# bidirectional-motor-driver.net
KiCad netlist of a schematic drawn in EAGLE
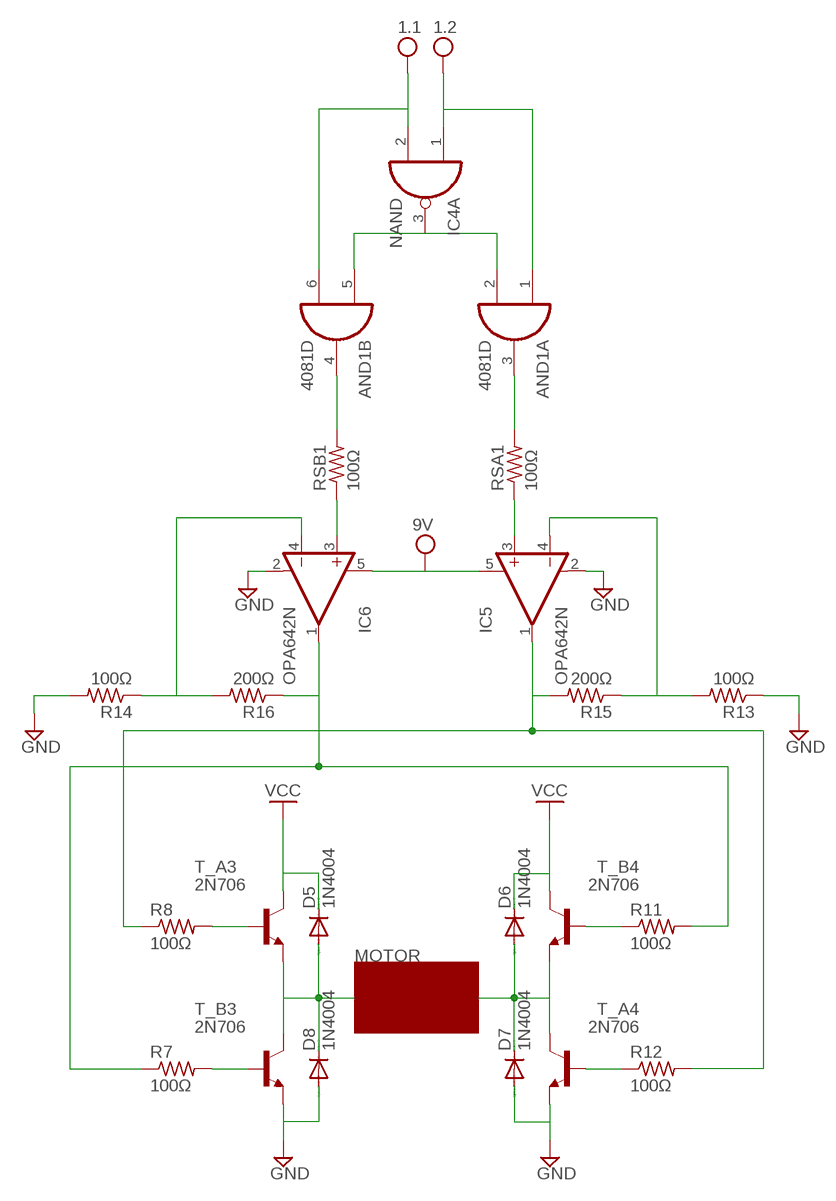
[diagram p0: schematic, sheet 1]

(export (version "E")
  (design (tool "Eeschema 10.0.6"))
  (components
    (comp (ref "AND1")
      (value "4081D")
      (footprint "eagle-import:SO14")
      (libsource (lib "eagle-import") (part "4081D"))
    )
    (comp (ref "D5")
      (value "1N4004")
      (footprint "eagle-import:DO41-10")
      (libsource (lib "eagle-import") (part "1N4004"))
    )
    (comp (ref "D6")
      (value "1N4004")
      (footprint "eagle-import:DO41-10")
      (libsource (lib "eagle-import") (part "1N4004"))
    )
    (comp (ref "D7")
      (value "1N4004")
      (footprint "eagle-import:DO41-10")
      (libsource (lib "eagle-import") (part "1N4004"))
    )
    (comp (ref "D8")
      (value "1N4004")
      (footprint "eagle-import:DO41-10")
      (libsource (lib "eagle-import") (part "1N4004"))
    )
    (comp (ref "IC4")
      (value "NAND")
      (footprint "eagle-import:SO14")
      (libsource (lib "eagle-import") (part "4011D"))
    )
    (comp (ref "IC5")
      (value "OPA642N")
      (footprint "eagle-import:SOT23-5")
      (libsource (lib "eagle-import") (part "OPA642N"))
    )
    (comp (ref "IC6")
      (value "OPA642N")
      (footprint "eagle-import:SOT23-5")
      (libsource (lib "eagle-import") (part "OPA642N"))
    )
    (comp (ref "R7")
      (value "100Ω")
      (footprint "eagle-import:0204V")
      (libsource (lib "eagle-import") (part "R-US_0204/2V"))
    )
    (comp (ref "R8")
      (value "100Ω")
      (footprint "eagle-import:0204V")
      (libsource (lib "eagle-import") (part "R-US_0204/2V"))
    )
    (comp (ref "R11")
      (value "100Ω")
      (footprint "eagle-import:0204V")
      (libsource (lib "eagle-import") (part "R-US_0204/2V"))
    )
    (comp (ref "R12")
      (value "100Ω")
      (footprint "eagle-import:0204V")
      (libsource (lib "eagle-import") (part "R-US_0204/2V"))
    )
    (comp (ref "R13")
      (value "100Ω")
      (footprint "eagle-import:0204V")
      (libsource (lib "eagle-import") (part "R-US_0204/2V"))
    )
    (comp (ref "R14")
      (value "100Ω")
      (footprint "eagle-import:0204V")
      (libsource (lib "eagle-import") (part "R-US_0204/2V"))
    )
    (comp (ref "R15")
      (value "200Ω")
      (footprint "eagle-import:0204V")
      (libsource (lib "eagle-import") (part "R-US_0204/2V"))
    )
    (comp (ref "R16")
      (value "200Ω")
      (footprint "eagle-import:0204V")
      (libsource (lib "eagle-import") (part "R-US_0204/2V"))
    )
    (comp (ref "RSA1")
      (value "100Ω")
      (footprint "eagle-import:0204V")
      (libsource (lib "eagle-import") (part "R-US_0204/2V"))
    )
    (comp (ref "RSB1")
      (value "100Ω")
      (footprint "eagle-import:0204V")
      (libsource (lib "eagle-import") (part "R-US_0204/2V"))
    )
    (comp (ref "T_A3")
      (value "2N706")
      (footprint "eagle-import:TO18")
      (libsource (lib "eagle-import") (part "2N706"))
    )
    (comp (ref "T_A4")
      (value "2N706")
      (footprint "eagle-import:TO18")
      (libsource (lib "eagle-import") (part "2N706"))
    )
    (comp (ref "T_B3")
      (value "2N706")
      (footprint "eagle-import:TO18")
      (libsource (lib "eagle-import") (part "2N706"))
    )
    (comp (ref "T_B4")
      (value "2N706")
      (footprint "eagle-import:TO18")
      (libsource (lib "eagle-import") (part "2N706"))
    )
  )
  (nets
    (net (code "1") (name "1.1") (class "Default")
      (node (ref "AND1") (pin "1") (pinfunction "I0_1") (pintype "input"))
      (node (ref "AND1") (pin "6") (pinfunction "I1_6") (pintype "input"))
      (node (ref "IC4") (pin "1") (pinfunction "I0_1") (pintype "input"))
      (node (ref "IC4") (pin "2") (pinfunction "I1_2") (pintype "input"))
    )
    (net (code "3") (name "GND") (class "Default")
      (node (ref "D7") (pin "A") (pinfunction "A_A") (pintype "passive"))
      (node (ref "D8") (pin "A") (pinfunction "A_A") (pintype "passive"))
      (node (ref "IC5") (pin "2") (pinfunction "V-_2") (pintype "power_in"))
      (node (ref "IC6") (pin "2") (pinfunction "V-_2") (pintype "power_in"))
      (node (ref "R13") (pin "1") (pinfunction "1_1") (pintype "passive"))
      (node (ref "R14") (pin "2") (pinfunction "2_2") (pintype "passive"))
      (node (ref "T_A4") (pin "1") (pinfunction "E_1") (pintype "passive"))
      (node (ref "T_B3") (pin "1") (pinfunction "E_1") (pintype "passive"))
    )
    (net (code "4") (name "Net-(AND1A-I1)") (class "Default")
      (node (ref "AND1") (pin "2") (pinfunction "I1_2") (pintype "input"))
      (node (ref "AND1") (pin "5") (pinfunction "I0_5") (pintype "input"))
      (node (ref "IC4") (pin "3") (pinfunction "O_3") (pintype "output"))
    )
    (net (code "5") (name "Net-(AND1A-O)") (class "Default")
      (node (ref "AND1") (pin "3") (pinfunction "O_3") (pintype "output"))
      (node (ref "RSA1") (pin "2") (pinfunction "2_2") (pintype "passive"))
    )
    (net (code "6") (name "Net-(AND1B-O)") (class "Default")
      (node (ref "AND1") (pin "4") (pinfunction "O_4") (pintype "output"))
      (node (ref "RSB1") (pin "2") (pinfunction "2_2") (pintype "passive"))
    )
    (net (code "7") (name "Net-(IC5-+IN)") (class "Default")
      (node (ref "IC5") (pin "3") (pinfunction "+IN_3") (pintype "input"))
      (node (ref "RSA1") (pin "1") (pinfunction "1_1") (pintype "passive"))
    )
    (net (code "8") (name "Net-(IC5-OUT)") (class "Default")
      (node (ref "IC5") (pin "1") (pinfunction "OUT_1") (pintype "output"))
      (node (ref "R12") (pin "2") (pinfunction "2_2") (pintype "passive"))
      (node (ref "R8") (pin "1") (pinfunction "1_1") (pintype "passive"))
    )
    (net (code "9") (name "Net-(IC5-V+)") (class "Default")
      (node (ref "IC5") (pin "5") (pinfunction "V+_5") (pintype "power_in"))
      (node (ref "IC6") (pin "5") (pinfunction "V+_5") (pintype "power_in"))
    )
    (net (code "10") (name "Net-(IC6-+IN)") (class "Default")
      (node (ref "IC6") (pin "3") (pinfunction "+IN_3") (pintype "input"))
      (node (ref "RSB1") (pin "1") (pinfunction "1_1") (pintype "passive"))
    )
    (net (code "11") (name "Net-(IC6-OUT)") (class "Default")
      (node (ref "IC6") (pin "1") (pinfunction "OUT_1") (pintype "output"))
      (node (ref "R11") (pin "2") (pinfunction "2_2") (pintype "passive"))
      (node (ref "R7") (pin "1") (pinfunction "1_1") (pintype "passive"))
    )
    (net (code "12") (name "Net-(R13-Pad2)") (class "Default")
      (node (ref "R13") (pin "2") (pinfunction "2_2") (pintype "passive"))
      (node (ref "R15") (pin "1") (pinfunction "1_1") (pintype "passive"))
    )
    (net (code "13") (name "Net-(R14-Pad1)") (class "Default")
      (node (ref "R14") (pin "1") (pinfunction "1_1") (pintype "passive"))
      (node (ref "R16") (pin "2") (pinfunction "2_2") (pintype "passive"))
    )
    (net (code "14") (name "Net-(T_A3-B)") (class "Default")
      (node (ref "R8") (pin "2") (pinfunction "2_2") (pintype "passive"))
      (node (ref "T_A3") (pin "2") (pinfunction "B_2") (pintype "passive"))
    )
    (net (code "15") (name "Net-(T_A3-E)") (class "Default")
      (node (ref "D5") (pin "A") (pinfunction "A_A") (pintype "passive"))
      (node (ref "D8") (pin "C") (pinfunction "C_C") (pintype "passive"))
      (node (ref "T_A3") (pin "1") (pinfunction "E_1") (pintype "passive"))
      (node (ref "T_B3") (pin "3") (pinfunction "C_3") (pintype "passive"))
    )
    (net (code "16") (name "Net-(T_A4-B)") (class "Default")
      (node (ref "R12") (pin "1") (pinfunction "1_1") (pintype "passive"))
      (node (ref "T_A4") (pin "2") (pinfunction "B_2") (pintype "passive"))
    )
    (net (code "17") (name "Net-(T_A4-C)") (class "Default")
      (node (ref "D6") (pin "A") (pinfunction "A_A") (pintype "passive"))
      (node (ref "D7") (pin "C") (pinfunction "C_C") (pintype "passive"))
      (node (ref "T_A4") (pin "3") (pinfunction "C_3") (pintype "passive"))
      (node (ref "T_B4") (pin "1") (pinfunction "E_1") (pintype "passive"))
    )
    (net (code "18") (name "Net-(T_B3-B)") (class "Default")
      (node (ref "R7") (pin "2") (pinfunction "2_2") (pintype "passive"))
      (node (ref "T_B3") (pin "2") (pinfunction "B_2") (pintype "passive"))
    )
    (net (code "19") (name "Net-(T_B4-B)") (class "Default")
      (node (ref "R11") (pin "1") (pinfunction "1_1") (pintype "passive"))
      (node (ref "T_B4") (pin "2") (pinfunction "B_2") (pintype "passive"))
    )
    (net (code "20") (name "VCC") (class "Default")
      (node (ref "D5") (pin "C") (pinfunction "C_C") (pintype "passive"))
      (node (ref "D6") (pin "C") (pinfunction "C_C") (pintype "passive"))
      (node (ref "T_A3") (pin "3") (pinfunction "C_3") (pintype "passive"))
      (node (ref "T_B4") (pin "3") (pinfunction "C_3") (pintype "passive"))
    )
    (net (code "21") (name "unconnected-(IC5--IN-Pad4)") (class "Default")
      (node (ref "IC5") (pin "4") (pinfunction "-IN_4") (pintype "input"))
    )
    (net (code "22") (name "unconnected-(IC6--IN-Pad4)") (class "Default")
      (node (ref "IC6") (pin "4") (pinfunction "-IN_4") (pintype "input"))
    )
    (net (code "23") (name "unconnected-(R15-Pad2)") (class "Default")
      (node (ref "R15") (pin "2") (pinfunction "2_2") (pintype "passive"))
    )
    (net (code "24") (name "unconnected-(R16-Pad1)") (class "Default")
      (node (ref "R16") (pin "1") (pinfunction "1_1") (pintype "passive"))
    )
  )
)
